# SCH1_Main.net
KiCad netlist of a schematic drawn in Altium Designer
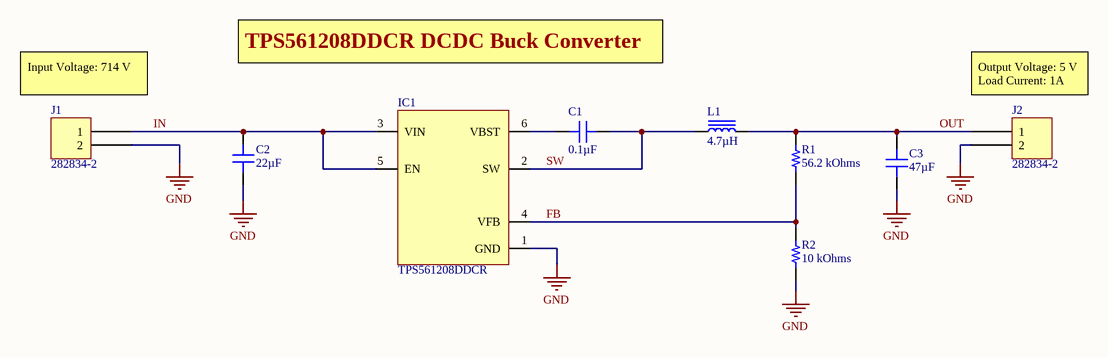
[diagram p0: SCH1_Main.SchDoc]

(export (version "E")
  (design (tool "Eeschema 10.0.6"))
  (components
    (comp (ref "C1")
      (value "0.1µF")
      (footprint "CAP 0805_2012")
      (description "CAP CER 0.1UF 50V X7R 0805")
      (fields (field (name "PART NUMBER") "CC0805MRX7R9BB104") (field (name "MANUFACTURER") "Yageo"))
      (libsource (lib "Celestial Altium Library - altium_library") (part "Capacitor"))
    )
    (comp (ref "C2")
      (value "22µF")
      (footprint "CAP 0805_2012")
      (description "CAP CER 22UF 16V X5R 0805")
      (fields
        (field (name "PART NUMBER") "CL21A226KOQNNNG")
        (field (name "MANUFACTURER") "Samsung Electro-Mechanics")
      )
      (libsource (lib "Celestial Altium Library - altium_library") (part "Capacitor"))
    )
    (comp (ref "C3")
      (value "47µF")
      (footprint "CAP 1210_3225 - 2.8MM")
      (description "CAP CER 47UF 16V X6S 1210")
      (fields
        (field (name "PART NUMBER") "GRM32EC81C476KE15L")
        (field (name "MANUFACTURER") "Murata Electronics")
      )
      (libsource (lib "Celestial Altium Library - altium_library") (part "Capacitor"))
    )
    (comp (ref "IC1")
      (value "TPS561208DDCR")
      (footprint "SOT95P280X110-6N")
      (description "Buck Switching Regulator IC Positive Adjustable 0.76V 1 Output 1A SOT-23-6 Thin, TSOT-23-6")
      (libsource (lib "SCH_Lib") (part "TPS561208DDCR"))
    )
    (comp (ref "J1")
      (value "282834-2")
      (footprint "TE 282834-2")
      (description "TERM BLK 2P SIDE ENT 2.54MM PCB")
      (fields (field (name "MANUFACTURER") "TE Connectivity AMP Connectors") (field (name "VOLTAGE") "150V"))
      (libsource (lib "") (part "2 Pin_1"))
    )
    (comp (ref "J2")
      (value "282834-2")
      (footprint "TE 282834-2")
      (description "TERM BLK 2P SIDE ENT 2.54MM PCB")
      (fields (field (name "MANUFACTURER") "TE Connectivity AMP Connectors") (field (name "VOLTAGE") "150V"))
      (libsource (lib "Celestial Altium Library - altium_library") (part "2 Pin"))
    )
    (comp (ref "L1")
      (value "4.7µH")
      (footprint "TDK SPM3012-LR")
      (description "FIXED IND 4.7UH 1.8A 199.1 MOHM")
      (fields (field (name "PART NUMBER") "SPM3015T-4R7M-LR") (field (name "MANUFACTURER") "TDK Corporation"))
      (libsource (lib "Celestial Altium Library - altium_library") (part "Inductor"))
    )
    (comp (ref "R1")
      (value "56.2 kOhms")
      (footprint "RES 0805_2012")
      (description "RES SMD 56.2K OHM 0.1% 1/4W 0805")
      (fields
        (field (name "PART NUMBER") "7-2176093-1")
        (field (name "MANUFACTURER") "TE Connectivity Passive Product")
      )
      (libsource (lib "Celestial Altium Library - altium_library") (part "Resistor"))
    )
    (comp (ref "R2")
      (value "10 kOhms")
      (footprint "RES 0805_2012")
      (description "RES SMD 10K OHM 1% 1/8W 0805")
      (fields (field (name "PART NUMBER") "AT0805FRE0710KL") (field (name "MANUFACTURER") "Yageo"))
      (libsource (lib "Celestial Altium Library - altium_library") (part "Resistor"))
    )
  )
  (nets
    (net (code "1") (name "/FB") (class "Default")
      (node (ref "IC1") (pin "4") (pinfunction "VFB_4") (pintype "passive"))
      (node (ref "R1") (pin "1") (pinfunction "1_1") (pintype "passive"))
      (node (ref "R2") (pin "2") (pinfunction "2_2") (pintype "passive"))
    )
    (net (code "2") (name "/IN") (class "Default")
      (node (ref "C2") (pin "2") (pinfunction "2_2") (pintype "passive"))
      (node (ref "IC1") (pin "3") (pinfunction "VIN_3") (pintype "passive"))
      (node (ref "IC1") (pin "5") (pinfunction "EN_5") (pintype "passive"))
      (node (ref "J1") (pin "1") (pinfunction "1_1") (pintype "passive"))
    )
    (net (code "3") (name "/OUT") (class "Default")
      (node (ref "C3") (pin "2") (pinfunction "2_2") (pintype "passive"))
      (node (ref "J2") (pin "1") (pinfunction "1_1") (pintype "passive"))
      (node (ref "L1") (pin "2") (pinfunction "2_2") (pintype "passive"))
      (node (ref "R1") (pin "2") (pinfunction "2_2") (pintype "passive"))
    )
    (net (code "4") (name "/SW") (class "Default")
      (node (ref "C1") (pin "2") (pinfunction "2_2") (pintype "passive"))
      (node (ref "IC1") (pin "2") (pinfunction "SW_2") (pintype "passive"))
      (node (ref "L1") (pin "1") (pinfunction "1_1") (pintype "passive"))
    )
    (net (code "5") (name "GND") (class "Default")
      (node (ref "C2") (pin "1") (pinfunction "1_1") (pintype "passive"))
      (node (ref "C3") (pin "1") (pinfunction "1_1") (pintype "passive"))
      (node (ref "IC1") (pin "1") (pinfunction "GND_1") (pintype "passive"))
      (node (ref "J1") (pin "2") (pinfunction "2_2") (pintype "passive"))
      (node (ref "J2") (pin "2") (pinfunction "2_2") (pintype "passive"))
      (node (ref "R2") (pin "1") (pinfunction "1_1") (pintype "passive"))
    )
    (net (code "6") (name "Net-(IC1-VBST)") (class "Default")
      (node (ref "C1") (pin "1") (pinfunction "1_1") (pintype "passive"))
      (node (ref "IC1") (pin "6") (pinfunction "VBST_6") (pintype "passive"))
    )
  )
)
